# 1-TX510_KIT.net
KiCad netlist of a schematic drawn in Altium Designer
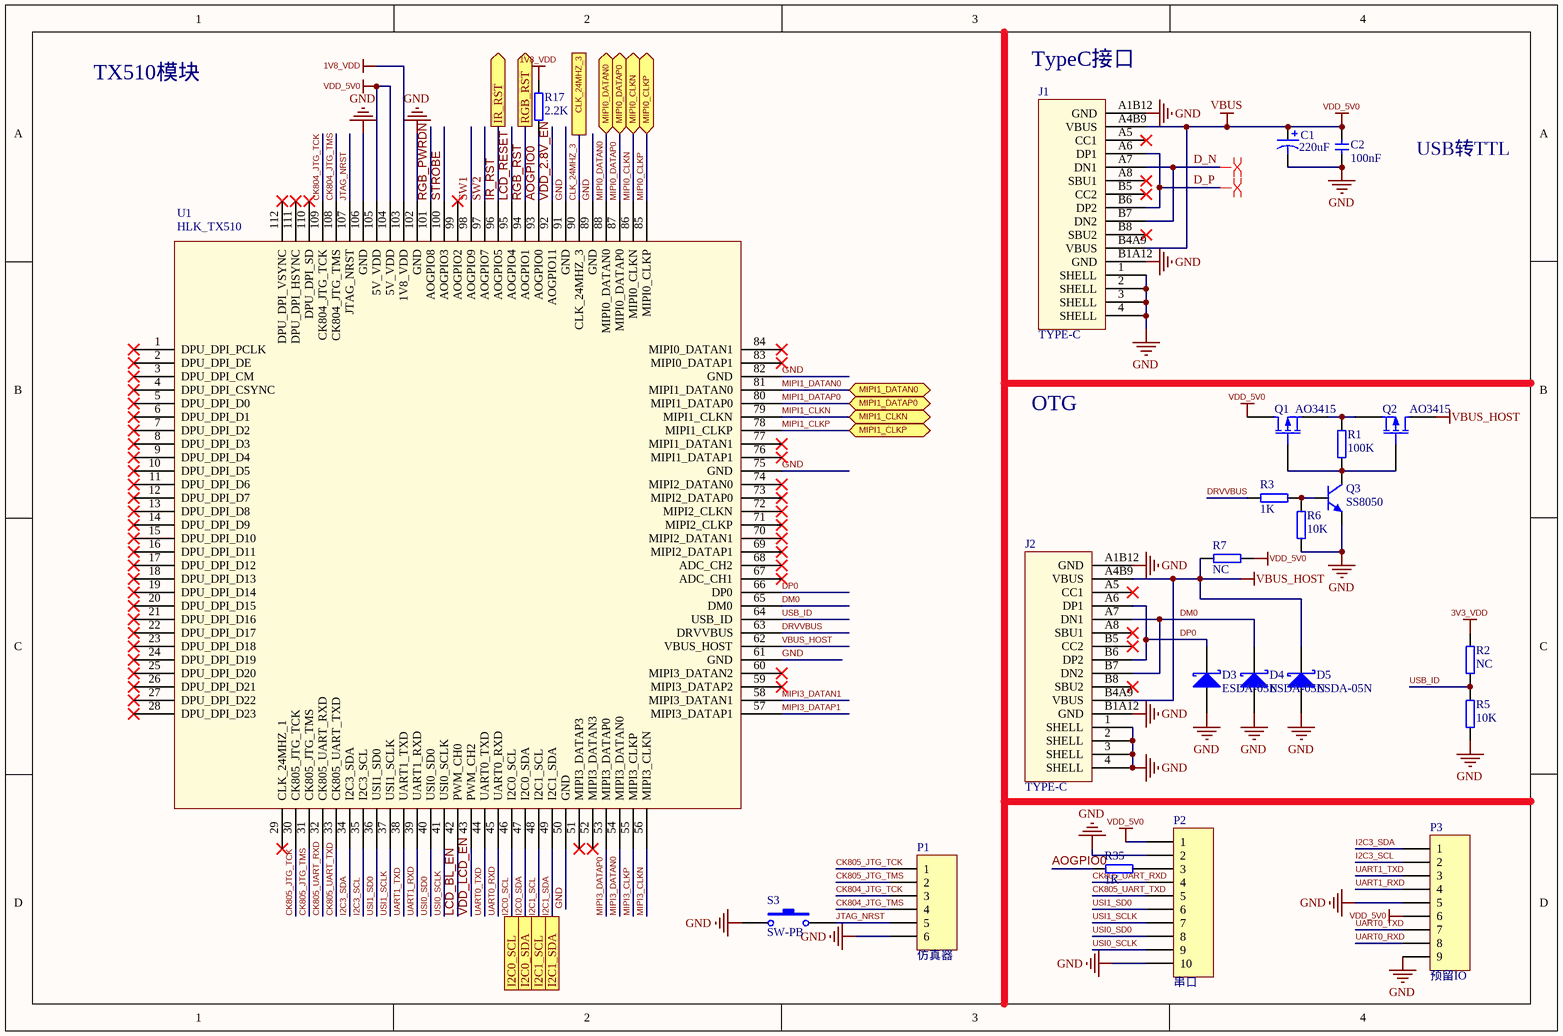
[diagram p0: 1-TX510_KIT.SchDoc]

(export (version "E")
  (design (tool "Eeschema 10.0.6"))
  (components
    (comp (ref "C1")
      (value "220uF")
      (footprint "SMD,6.3x7.7mm")
      (description "Polarized Capacitor (Radial)")
      (fields (field (name "Comment") "Cap Pol1") (field (name "PUBLISHER") "Altium Limited"))
      (libsource (lib "Miscellaneous Devices") (part "Cap Pol1"))
    )
    (comp (ref "C2")
      (value "100nF")
      (footprint "C0402")
      (description "C?")
      (libsource (lib "HNCY_SCH_Lib") (part "CAP1"))
    )
    (comp (ref "D3")
      (value "ESDA-05N")
      (footprint "R0402")
      (description "Silicon AF Schottky Diode for High-Speed Switching")
      (fields (field (name "PUBLISHER") "Altium Limited"))
      (libsource (lib "Miscellaneous Devices") (part "Diode BAS70"))
    )
    (comp (ref "D4")
      (value "ESDA-05N")
      (footprint "R0402")
      (description "Silicon AF Schottky Diode for High-Speed Switching")
      (fields (field (name "PUBLISHER") "Altium Limited"))
      (libsource (lib "Miscellaneous Devices") (part "Diode BAS70"))
    )
    (comp (ref "D5")
      (value "ESDA-05N")
      (footprint "R0402")
      (description "Silicon AF Schottky Diode for High-Speed Switching")
      (fields (field (name "PUBLISHER") "Altium Limited"))
      (libsource (lib "Miscellaneous Devices") (part "Diode BAS70"))
    )
    (comp (ref "J1") (value "TYPE-C") (footprint "TYPE-C16PIN") (libsource (lib "*") (part "TYPE-C16PIN")))
    (comp (ref "J2") (value "TYPE-C") (footprint "TYPE-C16PIN") (libsource (lib "*") (part "TYPE-C16PIN")))
    (comp (ref "P1")
      (value "仿真器")
      (footprint "HDR1X6")
      (description "Header, 6-Pin")
      (fields (field (name "PUBLISHER") "Altium Limited"))
      (libsource (lib "Miscellaneous Connectors") (part "Header 6"))
    )
    (comp (ref "P2")
      (value "串口")
      (footprint "HDR1X10")
      (description "Header, 10-Pin")
      (fields (field (name "PUBLISHER") "Altium Limited"))
      (libsource (lib "Miscellaneous Connectors") (part "Header 10"))
    )
    (comp (ref "P3")
      (value "预留IO")
      (footprint "HDR1X9")
      (description "Header, 9-Pin")
      (fields (field (name "PUBLISHER") "Altium Limited"))
      (libsource (lib "Miscellaneous Connectors") (part "Header 9"))
    )
    (comp (ref "Q1") (value "AO3415") (footprint "SOT-23") (libsource (lib "*") (part "AO3415")))
    (comp (ref "Q2") (value "AO3415") (footprint "SOT-23") (libsource (lib "*") (part "AO3415")))
    (comp (ref "Q3")
      (value "SS8050")
      (footprint "SOT23-BEC")
      (description "贴片三极管")
      (libsource (lib "HNCY_SCH_Lib") (part "NPN"))
    )
    (comp (ref "R1")
      (value "100K")
      (footprint "R0402")
      (description "R?")
      (libsource (lib "HNCY_SCH_Lib") (part "RES1"))
    )
    (comp (ref "R2")
      (value "NC")
      (footprint "R0402")
      (description "R?")
      (libsource (lib "HNCY_SCH_Lib") (part "RES1"))
    )
    (comp (ref "R3")
      (value "1K")
      (footprint "R0402")
      (description "R?")
      (libsource (lib "HNCY_SCH_Lib") (part "RES1"))
    )
    (comp (ref "R5")
      (value "10K")
      (footprint "R0402")
      (description "R?")
      (libsource (lib "HNCY_SCH_Lib") (part "RES1"))
    )
    (comp (ref "R6")
      (value "10K")
      (footprint "R0402")
      (description "R?")
      (libsource (lib "HNCY_SCH_Lib") (part "RES1"))
    )
    (comp (ref "R7")
      (value "NC")
      (footprint "RES_0603")
      (description "R?")
      (libsource (lib "HNCY_SCH_Lib") (part "RES1"))
    )
    (comp (ref "R17")
      (value "2.2K")
      (footprint "R0402")
      (description "R?")
      (libsource (lib "HNCY_SCH_Lib") (part "RES1"))
    )
    (comp (ref "R35")
      (value "1K")
      (footprint "R0402")
      (description "R?")
      (libsource (lib "HNCY_SCH_Lib") (part "RES1"))
    )
    (comp (ref "S3")
      (value "SW-PB")
      (footprint "轻触开关4.5x4.5")
      (description "Switch")
      (fields (field (name "PUBLISHER") "Altium Limited"))
      (libsource (lib "Miscellaneous Devices") (part "SW-PB"))
    )
    (comp (ref "U1")
      (value "HLK_TX510")
      (footprint "HLK_TX510 _KIT")
      (libsource (lib "MY SCHLIB") (part "HLK_TX510"))
    )
  )
  (nets
    (net (code "1") (name "/AOGPIO0") (class "Default")
      (node (ref "R17") (pin "1") (pinfunction "1_1") (pintype "passive"))
      (node (ref "R35") (pin "2") (pinfunction "2_2") (pintype "passive"))
      (node (ref "U1") (pin "93") (pinfunction "AOGPIO0_93") (pintype "passive"))
    )
    (net (code "2") (name "/CK804_JTG_TCK") (class "Default")
      (node (ref "P1") (pin "3") (pinfunction "3_3") (pintype "passive"))
      (node (ref "U1") (pin "109") (pinfunction "CK804_JTG_TCK_109") (pintype "passive"))
    )
    (net (code "3") (name "/CK804_JTG_TMS") (class "Default")
      (node (ref "P1") (pin "4") (pinfunction "4_4") (pintype "passive"))
      (node (ref "U1") (pin "108") (pinfunction "CK804_JTG_TMS_108") (pintype "passive"))
    )
    (net (code "4") (name "/CK805_JTG_TCK") (class "Default")
      (node (ref "P1") (pin "1") (pinfunction "1_1") (pintype "passive"))
      (node (ref "U1") (pin "30") (pinfunction "CK805_JTG_TCK_30") (pintype "passive"))
    )
    (net (code "5") (name "/CK805_JTG_TMS") (class "Default")
      (node (ref "P1") (pin "2") (pinfunction "2_2") (pintype "passive"))
      (node (ref "U1") (pin "31") (pinfunction "CK805_JTG_TMS_31") (pintype "passive"))
    )
    (net (code "6") (name "/CK805_UART_RXD") (class "Default")
      (node (ref "P2") (pin "4") (pinfunction "4_4") (pintype "passive"))
      (node (ref "U1") (pin "32") (pinfunction "CK805_UART_RXD_32") (pintype "passive"))
    )
    (net (code "7") (name "/CK805_UART_TXD") (class "Default")
      (node (ref "P2") (pin "5") (pinfunction "5_5") (pintype "passive"))
      (node (ref "U1") (pin "33") (pinfunction "CK805_UART_TXD_33") (pintype "passive"))
    )
    (net (code "8") (name "/CLK_24MHZ_3") (class "Default")
      (node (ref "U1") (pin "90") (pinfunction "CLK_24MHZ_3_90") (pintype "passive"))
    )
    (net (code "9") (name "/DM0") (class "Default")
      (node (ref "D4") (pin "2") (pinfunction "K_2") (pintype "passive"))
      (node (ref "J2") (pin "A7") (pinfunction "DN1_A7") (pintype "passive"))
      (node (ref "J2") (pin "B7") (pinfunction "DN2_B7") (pintype "passive"))
      (node (ref "U1") (pin "65") (pinfunction "DM0_65") (pintype "passive"))
    )
    (net (code "10") (name "/DP0") (class "Default")
      (node (ref "D3") (pin "2") (pinfunction "K_2") (pintype "passive"))
      (node (ref "J2") (pin "A6") (pinfunction "DP1_A6") (pintype "passive"))
      (node (ref "J2") (pin "B6") (pinfunction "DP2_B6") (pintype "passive"))
      (node (ref "U1") (pin "66") (pinfunction "DP0_66") (pintype "passive"))
    )
    (net (code "11") (name "/DRVVBUS") (class "Default")
      (node (ref "R3") (pin "2") (pinfunction "2_2") (pintype "passive"))
      (node (ref "U1") (pin "63") (pinfunction "DRVVBUS_63") (pintype "passive"))
    )
    (net (code "12") (name "/D_N") (class "Default")
      (node (ref "J1") (pin "A7") (pinfunction "DN1_A7") (pintype "passive"))
      (node (ref "J1") (pin "B7") (pinfunction "DN2_B7") (pintype "passive"))
    )
    (net (code "13") (name "/D_P") (class "Default")
      (node (ref "J1") (pin "A6") (pinfunction "DP1_A6") (pintype "passive"))
      (node (ref "J1") (pin "B6") (pinfunction "DP2_B6") (pintype "passive"))
    )
    (net (code "14") (name "/I2C0_SCL") (class "Default")
      (node (ref "U1") (pin "46") (pinfunction "I2C0_SCL_46") (pintype "passive"))
    )
    (net (code "15") (name "/I2C0_SDA") (class "Default")
      (node (ref "U1") (pin "47") (pinfunction "I2C0_SDA_47") (pintype "passive"))
    )
    (net (code "16") (name "/I2C1_SCL") (class "Default")
      (node (ref "U1") (pin "48") (pinfunction "I2C1_SCL_48") (pintype "passive"))
    )
    (net (code "17") (name "/I2C1_SDA") (class "Default")
      (node (ref "U1") (pin "49") (pinfunction "I2C1_SDA_49") (pintype "passive"))
    )
    (net (code "18") (name "/I2C3_SCL") (class "Default")
      (node (ref "P3") (pin "2") (pinfunction "2_2") (pintype "passive"))
      (node (ref "U1") (pin "35") (pinfunction "I2C3_SCL_35") (pintype "passive"))
    )
    (net (code "19") (name "/I2C3_SDA") (class "Default")
      (node (ref "P3") (pin "1") (pinfunction "1_1") (pintype "passive"))
      (node (ref "U1") (pin "34") (pinfunction "I2C3_SDA_34") (pintype "passive"))
    )
    (net (code "20") (name "/IR_RST") (class "Default")
      (node (ref "U1") (pin "96") (pinfunction "AOGPIO5_96") (pintype "passive"))
    )
    (net (code "21") (name "/JTAG_NRST") (class "Default")
      (node (ref "P1") (pin "5") (pinfunction "5_5") (pintype "passive"))
      (node (ref "S3") (pin "2") (pinfunction "2_2") (pintype "passive"))
      (node (ref "U1") (pin "107") (pinfunction "JTAG_NRST_107") (pintype "passive"))
    )
    (net (code "22") (name "/LCD_BL_EN") (class "Default")
      (node (ref "U1") (pin "42") (pinfunction "PWM_CH0_42") (pintype "passive"))
    )
    (net (code "23") (name "/LCD_RESET") (class "Default")
      (node (ref "U1") (pin "95") (pinfunction "AOGPIO4_95") (pintype "passive"))
    )
    (net (code "24") (name "/MIPI0_CLKN") (class "Default")
      (node (ref "U1") (pin "86") (pinfunction "MIPI0_CLKN_86") (pintype "passive"))
    )
    (net (code "25") (name "/MIPI0_CLKP") (class "Default")
      (node (ref "U1") (pin "85") (pinfunction "MIPI0_CLKP_85") (pintype "passive"))
    )
    (net (code "26") (name "/MIPI0_DATAN0") (class "Default")
      (node (ref "U1") (pin "88") (pinfunction "MIPI0_DATAN0_88") (pintype "passive"))
    )
    (net (code "27") (name "/MIPI0_DATAP0") (class "Default")
      (node (ref "U1") (pin "87") (pinfunction "MIPI0_DATAP0_87") (pintype "passive"))
    )
    (net (code "28") (name "/MIPI1_CLKN") (class "Default")
      (node (ref "U1") (pin "79") (pinfunction "MIPI1_CLKN_79") (pintype "passive"))
    )
    (net (code "29") (name "/MIPI1_CLKP") (class "Default")
      (node (ref "U1") (pin "78") (pinfunction "MIPI1_CLKP_78") (pintype "passive"))
    )
    (net (code "30") (name "/MIPI1_DATAN0") (class "Default")
      (node (ref "U1") (pin "81") (pinfunction "MIPI1_DATAN0_81") (pintype "passive"))
    )
    (net (code "31") (name "/MIPI1_DATAP0") (class "Default")
      (node (ref "U1") (pin "80") (pinfunction "MIPI1_DATAP0_80") (pintype "passive"))
    )
    (net (code "32") (name "/MIPI3_CLKN") (class "Default")
      (node (ref "U1") (pin "56") (pinfunction "MIPI3_CLKN_56") (pintype "passive"))
    )
    (net (code "33") (name "/MIPI3_CLKP") (class "Default")
      (node (ref "U1") (pin "55") (pinfunction "MIPI3_CLKP_55") (pintype "passive"))
    )
    (net (code "34") (name "/MIPI3_DATAN0") (class "Default")
      (node (ref "U1") (pin "54") (pinfunction "MIPI3_DATAN0_54") (pintype "passive"))
    )
    (net (code "35") (name "/MIPI3_DATAN1") (class "Default")
      (node (ref "U1") (pin "58") (pinfunction "MIPI3_DATAN1_58") (pintype "passive"))
    )
    (net (code "36") (name "/MIPI3_DATAP0") (class "Default")
      (node (ref "U1") (pin "53") (pinfunction "MIPI3_DATAP0_53") (pintype "passive"))
    )
    (net (code "37") (name "/MIPI3_DATAP1") (class "Default")
      (node (ref "U1") (pin "57") (pinfunction "MIPI3_DATAP1_57") (pintype "passive"))
    )
    (net (code "38") (name "/RGB_PWRDN") (class "Default")
      (node (ref "U1") (pin "101") (pinfunction "AOGPIO8_101") (pintype "passive"))
    )
    (net (code "39") (name "/RGB_RST") (class "Default")
      (node (ref "U1") (pin "94") (pinfunction "AOGPIO1_94") (pintype "passive"))
    )
    (net (code "40") (name "/STROBE") (class "Default")
      (node (ref "U1") (pin "100") (pinfunction "AOGPIO3_100") (pintype "passive"))
    )
    (net (code "41") (name "/SW1") (class "Default")
      (node (ref "U1") (pin "98") (pinfunction "AOGPIO9_98") (pintype "passive"))
    )
    (net (code "42") (name "/SW2") (class "Default")
      (node (ref "U1") (pin "97") (pinfunction "AOGPIO7_97") (pintype "passive"))
    )
    (net (code "43") (name "/UART0_RXD") (class "Default")
      (node (ref "P3") (pin "8") (pinfunction "8_8") (pintype "passive"))
      (node (ref "U1") (pin "45") (pinfunction "UART0_RXD_45") (pintype "passive"))
    )
    (net (code "44") (name "/UART0_TXD") (class "Default")
      (node (ref "P3") (pin "7") (pinfunction "7_7") (pintype "passive"))
      (node (ref "U1") (pin "44") (pinfunction "UART0_TXD_44") (pintype "passive"))
    )
    (net (code "45") (name "/UART1_RXD") (class "Default")
      (node (ref "P3") (pin "4") (pinfunction "4_4") (pintype "passive"))
      (node (ref "U1") (pin "39") (pinfunction "UART1_RXD_39") (pintype "passive"))
    )
    (net (code "46") (name "/UART1_TXD") (class "Default")
      (node (ref "P3") (pin "3") (pinfunction "3_3") (pintype "passive"))
      (node (ref "U1") (pin "38") (pinfunction "UART1_TXD_38") (pintype "passive"))
    )
    (net (code "47") (name "/USB_ID") (class "Default")
      (node (ref "R2") (pin "1") (pinfunction "1_1") (pintype "passive"))
      (node (ref "R5") (pin "2") (pinfunction "2_2") (pintype "passive"))
      (node (ref "U1") (pin "64") (pinfunction "USB_ID_64") (pintype "passive"))
    )
    (net (code "48") (name "/USI0_SCLK") (class "Default")
      (node (ref "P2") (pin "9") (pinfunction "9_9") (pintype "passive"))
      (node (ref "U1") (pin "41") (pinfunction "USI0_SCLK_41") (pintype "passive"))
    )
    (net (code "49") (name "/USI0_SD0") (class "Default")
      (node (ref "P2") (pin "8") (pinfunction "8_8") (pintype "passive"))
      (node (ref "U1") (pin "40") (pinfunction "USI0_SD0_40") (pintype "passive"))
    )
    (net (code "50") (name "/USI1_SCLK") (class "Default")
      (node (ref "P2") (pin "7") (pinfunction "7_7") (pintype "passive"))
      (node (ref "U1") (pin "37") (pinfunction "USI1_SCLK_37") (pintype "passive"))
    )
    (net (code "51") (name "/USI1_SD0") (class "Default")
      (node (ref "P2") (pin "6") (pinfunction "6_6") (pintype "passive"))
      (node (ref "U1") (pin "36") (pinfunction "USI1_SD0_36") (pintype "passive"))
    )
    (net (code "52") (name "/VDD_2.8V_EN") (class "Default")
      (node (ref "U1") (pin "92") (pinfunction "AOGPIO11_92") (pintype "passive"))
    )
    (net (code "53") (name "/VDD_LCD_EN") (class "Default")
      (node (ref "U1") (pin "43") (pinfunction "PWM_CH2_43") (pintype "passive"))
    )
    (net (code "54") (name "1V8_VDD") (class "Default")
      (node (ref "R17") (pin "2") (pinfunction "2_2") (pintype "passive"))
      (node (ref "U1") (pin "103") (pinfunction "1V8_VDD_103") (pintype "passive"))
    )
    (net (code "55") (name "3V3_VDD") (class "Default")
      (node (ref "R2") (pin "2") (pinfunction "2_2") (pintype "passive"))
    )
    (net (code "56") (name "GND") (class "Default")
      (node (ref "C1") (pin "2") (pinfunction "2_2") (pintype "passive"))
      (node (ref "C2") (pin "1") (pintype "passive"))
      (node (ref "D3") (pin "1") (pinfunction "A_1") (pintype "passive"))
      (node (ref "D4") (pin "1") (pinfunction "A_1") (pintype "passive"))
      (node (ref "D5") (pin "1") (pinfunction "A_1") (pintype "passive"))
      (node (ref "J1") (pin "1") (pinfunction "SHELL_1") (pintype "passive"))
      (node (ref "J1") (pin "2") (pinfunction "SHELL_2") (pintype "passive"))
      (node (ref "J1") (pin "3") (pinfunction "SHELL_3") (pintype "passive"))
      (node (ref "J1") (pin "4") (pinfunction "SHELL_4") (pintype "passive"))
      (node (ref "J1") (pin "A1B12") (pinfunction "GND_A1B12") (pintype "passive"))
      (node (ref "J1") (pin "B1A12") (pinfunction "GND_B1A12") (pintype "passive"))
      (node (ref "J2") (pin "1") (pinfunction "SHELL_1") (pintype "passive"))
      (node (ref "J2") (pin "2") (pinfunction "SHELL_2") (pintype "passive"))
      (node (ref "J2") (pin "3") (pinfunction "SHELL_3") (pintype "passive"))
      (node (ref "J2") (pin "4") (pinfunction "SHELL_4") (pintype "passive"))
      (node (ref "J2") (pin "A1B12") (pinfunction "GND_A1B12") (pintype "passive"))
      (node (ref "J2") (pin "B1A12") (pinfunction "GND_B1A12") (pintype "passive"))
      (node (ref "P1") (pin "6") (pinfunction "6_6") (pintype "passive"))
      (node (ref "P2") (pin "10") (pinfunction "10_10") (pintype "passive"))
      (node (ref "P2") (pin "2") (pinfunction "2_2") (pintype "passive"))
      (node (ref "P3") (pin "5") (pinfunction "5_5") (pintype "passive"))
      (node (ref "P3") (pin "9") (pinfunction "9_9") (pintype "passive"))
      (node (ref "Q3") (pin "E") (pinfunction "E_E") (pintype "passive"))
      (node (ref "R5") (pin "1") (pinfunction "1_1") (pintype "passive"))
      (node (ref "R6") (pin "1") (pinfunction "1_1") (pintype "passive"))
      (node (ref "S3") (pin "1") (pinfunction "1_1") (pintype "passive"))
      (node (ref "U1") (pin "102") (pinfunction "GND_102") (pintype "passive"))
      (node (ref "U1") (pin "106") (pinfunction "GND_106") (pintype "passive"))
      (node (ref "U1") (pin "50") (pinfunction "GND_50") (pintype "passive"))
      (node (ref "U1") (pin "61") (pinfunction "GND_61") (pintype "passive"))
      (node (ref "U1") (pin "75") (pinfunction "GND_75") (pintype "passive"))
      (node (ref "U1") (pin "82") (pinfunction "GND_82") (pintype "passive"))
      (node (ref "U1") (pin "89") (pinfunction "GND_89") (pintype "passive"))
      (node (ref "U1") (pin "91") (pinfunction "GND_91") (pintype "passive"))
    )
    (net (code "57") (name "Net-(P2-Pad3)") (class "Default")
      (node (ref "P2") (pin "3") (pinfunction "3_3") (pintype "passive"))
      (node (ref "R35") (pin "1") (pinfunction "1_1") (pintype "passive"))
    )
    (net (code "58") (name "Net-(Q1-G)") (class "Default")
      (node (ref "Q1") (pin "1") (pinfunction "G_1") (pintype "passive"))
      (node (ref "Q2") (pin "1") (pinfunction "G_1") (pintype "passive"))
      (node (ref "Q3") (pin "C") (pinfunction "C_C") (pintype "passive"))
      (node (ref "R1") (pin "1") (pinfunction "1_1") (pintype "passive"))
    )
    (net (code "59") (name "Net-(Q1-S)") (class "Default")
      (node (ref "Q1") (pin "2") (pinfunction "S_2") (pintype "passive"))
      (node (ref "Q2") (pin "2") (pinfunction "S_2") (pintype "passive"))
      (node (ref "R1") (pin "2") (pinfunction "2_2") (pintype "passive"))
    )
    (net (code "60") (name "Net-(Q3-PadB)") (class "Default")
      (node (ref "Q3") (pin "B") (pinfunction "B_B") (pintype "passive"))
      (node (ref "R3") (pin "1") (pinfunction "1_1") (pintype "passive"))
      (node (ref "R6") (pin "2") (pinfunction "2_2") (pintype "passive"))
    )
    (net (code "61") (name "VBUS") (class "Default")
      (node (ref "C1") (pin "1") (pinfunction "1_1") (pintype "passive"))
      (node (ref "C2") (pin "2") (pintype "passive"))
      (node (ref "J1") (pin "A4B9") (pinfunction "VBUS_A4B9") (pintype "passive"))
      (node (ref "J1") (pin "B4A9") (pinfunction "VBUS_B4A9") (pintype "passive"))
      (node (ref "P2") (pin "1") (pinfunction "1_1") (pintype "passive"))
      (node (ref "P3") (pin "6") (pinfunction "6_6") (pintype "passive"))
      (node (ref "Q1") (pin "3") (pinfunction "D_3") (pintype "passive"))
      (node (ref "R7") (pin "1") (pinfunction "1_1") (pintype "passive"))
      (node (ref "U1") (pin "104") (pinfunction "5V_VDD_104") (pintype "passive"))
      (node (ref "U1") (pin "105") (pinfunction "5V_VDD_105") (pintype "passive"))
    )
    (net (code "62") (name "VBUS_HOST") (class "Default")
      (node (ref "D5") (pin "2") (pinfunction "K_2") (pintype "passive"))
      (node (ref "J2") (pin "A4B9") (pinfunction "VBUS_A4B9") (pintype "passive"))
      (node (ref "J2") (pin "B4A9") (pinfunction "VBUS_B4A9") (pintype "passive"))
      (node (ref "Q2") (pin "3") (pinfunction "D_3") (pintype "passive"))
      (node (ref "R7") (pin "2") (pinfunction "2_2") (pintype "passive"))
      (node (ref "U1") (pin "62") (pinfunction "VBUS_HOST_62") (pintype "passive"))
    )
    (net (code "63") (name "unconnected-(J1-CC1-PadA5)") (class "Default")
      (node (ref "J1") (pin "A5") (pinfunction "CC1_A5") (pintype "passive+no_connect"))
    )
    (net (code "64") (name "unconnected-(J1-CC2-PadB5)") (class "Default")
      (node (ref "J1") (pin "B5") (pinfunction "CC2_B5") (pintype "passive+no_connect"))
    )
    (net (code "65") (name "unconnected-(J1-SBU1-PadA8)") (class "Default")
      (node (ref "J1") (pin "A8") (pinfunction "SBU1_A8") (pintype "passive+no_connect"))
    )
    (net (code "66") (name "unconnected-(J1-SBU2-PadB8)") (class "Default")
      (node (ref "J1") (pin "B8") (pinfunction "SBU2_B8") (pintype "passive+no_connect"))
    )
    (net (code "67") (name "unconnected-(J2-CC1-PadA5)") (class "Default")
      (node (ref "J2") (pin "A5") (pinfunction "CC1_A5") (pintype "passive+no_connect"))
    )
    (net (code "68") (name "unconnected-(J2-CC2-PadB5)") (class "Default")
      (node (ref "J2") (pin "B5") (pinfunction "CC2_B5") (pintype "passive+no_connect"))
    )
    (net (code "69") (name "unconnected-(J2-SBU1-PadA8)") (class "Default")
      (node (ref "J2") (pin "A8") (pinfunction "SBU1_A8") (pintype "passive+no_connect"))
    )
    (net (code "70") (name "unconnected-(J2-SBU2-PadB8)") (class "Default")
      (node (ref "J2") (pin "B8") (pinfunction "SBU2_B8") (pintype "passive+no_connect"))
    )
    (net (code "71") (name "unconnected-(U1-ADC_CH1-Pad67)") (class "Default")
      (node (ref "U1") (pin "67") (pinfunction "ADC_CH1_67") (pintype "passive+no_connect"))
    )
    (net (code "72") (name "unconnected-(U1-ADC_CH2-Pad68)") (class "Default")
      (node (ref "U1") (pin "68") (pinfunction "ADC_CH2_68") (pintype "passive+no_connect"))
    )
    (net (code "73") (name "unconnected-(U1-AOGPIO2-Pad99)") (class "Default")
      (node (ref "U1") (pin "99") (pinfunction "AOGPIO2_99") (pintype "passive+no_connect"))
    )
    (net (code "74") (name "unconnected-(U1-CLK_24MHZ_1-Pad29)") (class "Default")
      (node (ref "U1") (pin "29") (pinfunction "CLK_24MHZ_1_29") (pintype "passive+no_connect"))
    )
    (net (code "75") (name "unconnected-(U1-DPU_DPI_CM-Pad3)") (class "Default")
      (node (ref "U1") (pin "3") (pinfunction "DPU_DPI_CM_3") (pintype "passive+no_connect"))
    )
    (net (code "76") (name "unconnected-(U1-DPU_DPI_CSYNC-Pad4)") (class "Default")
      (node (ref "U1") (pin "4") (pinfunction "DPU_DPI_CSYNC_4") (pintype "passive+no_connect"))
    )
    (net (code "77") (name "unconnected-(U1-DPU_DPI_D0-Pad5)") (class "Default")
      (node (ref "U1") (pin "5") (pinfunction "DPU_DPI_D0_5") (pintype "passive+no_connect"))
    )
    (net (code "78") (name "unconnected-(U1-DPU_DPI_D1-Pad6)") (class "Default")
      (node (ref "U1") (pin "6") (pinfunction "DPU_DPI_D1_6") (pintype "passive+no_connect"))
    )
    (net (code "79") (name "unconnected-(U1-DPU_DPI_D2-Pad7)") (class "Default")
      (node (ref "U1") (pin "7") (pinfunction "DPU_DPI_D2_7") (pintype "passive+no_connect"))
    )
    (net (code "80") (name "unconnected-(U1-DPU_DPI_D3-Pad8)") (class "Default")
      (node (ref "U1") (pin "8") (pinfunction "DPU_DPI_D3_8") (pintype "passive+no_connect"))
    )
    (net (code "81") (name "unconnected-(U1-DPU_DPI_D4-Pad9)") (class "Default")
      (node (ref "U1") (pin "9") (pinfunction "DPU_DPI_D4_9") (pintype "passive+no_connect"))
    )
    (net (code "82") (name "unconnected-(U1-DPU_DPI_D5-Pad10)") (class "Default")
      (node (ref "U1") (pin "10") (pinfunction "DPU_DPI_D5_10") (pintype "passive+no_connect"))
    )
    (net (code "83") (name "unconnected-(U1-DPU_DPI_D6-Pad11)") (class "Default")
      (node (ref "U1") (pin "11") (pinfunction "DPU_DPI_D6_11") (pintype "passive+no_connect"))
    )
    (net (code "84") (name "unconnected-(U1-DPU_DPI_D7-Pad12)") (class "Default")
      (node (ref "U1") (pin "12") (pinfunction "DPU_DPI_D7_12") (pintype "passive+no_connect"))
    )
    (net (code "85") (name "unconnected-(U1-DPU_DPI_D8-Pad13)") (class "Default")
      (node (ref "U1") (pin "13") (pinfunction "DPU_DPI_D8_13") (pintype "passive+no_connect"))
    )
    (net (code "86") (name "unconnected-(U1-DPU_DPI_D9-Pad14)") (class "Default")
      (node (ref "U1") (pin "14") (pinfunction "DPU_DPI_D9_14") (pintype "passive+no_connect"))
    )
    (net (code "87") (name "unconnected-(U1-DPU_DPI_D10-Pad15)") (class "Default")
      (node (ref "U1") (pin "15") (pinfunction "DPU_DPI_D10_15") (pintype "passive+no_connect"))
    )
    (net (code "88") (name "unconnected-(U1-DPU_DPI_D11-Pad16)") (class "Default")
      (node (ref "U1") (pin "16") (pinfunction "DPU_DPI_D11_16") (pintype "passive+no_connect"))
    )
    (net (code "89") (name "unconnected-(U1-DPU_DPI_D12-Pad17)") (class "Default")
      (node (ref "U1") (pin "17") (pinfunction "DPU_DPI_D12_17") (pintype "passive+no_connect"))
    )
    (net (code "90") (name "unconnected-(U1-DPU_DPI_D13-Pad18)") (class "Default")
      (node (ref "U1") (pin "18") (pinfunction "DPU_DPI_D13_18") (pintype "passive+no_connect"))
    )
    (net (code "91") (name "unconnected-(U1-DPU_DPI_D14-Pad19)") (class "Default")
      (node (ref "U1") (pin "19") (pinfunction "DPU_DPI_D14_19") (pintype "passive+no_connect"))
    )
    (net (code "92") (name "unconnected-(U1-DPU_DPI_D15-Pad20)") (class "Default")
      (node (ref "U1") (pin "20") (pinfunction "DPU_DPI_D15_20") (pintype "passive+no_connect"))
    )
    (net (code "93") (name "unconnected-(U1-DPU_DPI_D16-Pad21)") (class "Default")
      (node (ref "U1") (pin "21") (pinfunction "DPU_DPI_D16_21") (pintype "passive+no_connect"))
    )
    (net (code "94") (name "unconnected-(U1-DPU_DPI_D17-Pad22)") (class "Default")
      (node (ref "U1") (pin "22") (pinfunction "DPU_DPI_D17_22") (pintype "passive+no_connect"))
    )
    (net (code "95") (name "unconnected-(U1-DPU_DPI_D18-Pad23)") (class "Default")
      (node (ref "U1") (pin "23") (pinfunction "DPU_DPI_D18_23") (pintype "passive+no_connect"))
    )
    (net (code "96") (name "unconnected-(U1-DPU_DPI_D19-Pad24)") (class "Default")
      (node (ref "U1") (pin "24") (pinfunction "DPU_DPI_D19_24") (pintype "passive+no_connect"))
    )
    (net (code "97") (name "unconnected-(U1-DPU_DPI_D20-Pad25)") (class "Default")
      (node (ref "U1") (pin "25") (pinfunction "DPU_DPI_D20_25") (pintype "passive+no_connect"))
    )
    (net (code "98") (name "unconnected-(U1-DPU_DPI_D21-Pad26)") (class "Default")
      (node (ref "U1") (pin "26") (pinfunction "DPU_DPI_D21_26") (pintype "passive+no_connect"))
    )
    (net (code "99") (name "unconnected-(U1-DPU_DPI_D22-Pad27)") (class "Default")
      (node (ref "U1") (pin "27") (pinfunction "DPU_DPI_D22_27") (pintype "passive+no_connect"))
    )
    (net (code "100") (name "unconnected-(U1-DPU_DPI_D23-Pad28)") (class "Default")
      (node (ref "U1") (pin "28") (pinfunction "DPU_DPI_D23_28") (pintype "passive+no_connect"))
    )
    (net (code "101") (name "unconnected-(U1-DPU_DPI_DE-Pad2)") (class "Default")
      (node (ref "U1") (pin "2") (pinfunction "DPU_DPI_DE_2") (pintype "passive+no_connect"))
    )
    (net (code "102") (name "unconnected-(U1-DPU_DPI_HSYNC-Pad111)") (class "Default")
      (node (ref "U1") (pin "111") (pinfunction "DPU_DPI_HSYNC_111") (pintype "passive+no_connect"))
    )
    (net (code "103") (name "unconnected-(U1-DPU_DPI_PCLK-Pad1)") (class "Default")
      (node (ref "U1") (pin "1") (pinfunction "DPU_DPI_PCLK_1") (pintype "passive+no_connect"))
    )
    (net (code "104") (name "unconnected-(U1-DPU_DPI_SD-Pad110)") (class "Default")
      (node (ref "U1") (pin "110") (pinfunction "DPU_DPI_SD_110") (pintype "passive+no_connect"))
    )
    (net (code "105") (name "unconnected-(U1-DPU_DPI_VSYNC-Pad112)") (class "Default")
      (node (ref "U1") (pin "112") (pinfunction "DPU_DPI_VSYNC_112") (pintype "passive+no_connect"))
    )
    (net (code "106") (name "unconnected-(U1-MIPI0_DATAN1-Pad84)") (class "Default")
      (node (ref "U1") (pin "84") (pinfunction "MIPI0_DATAN1_84") (pintype "passive+no_connect"))
    )
    (net (code "107") (name "unconnected-(U1-MIPI0_DATAP1-Pad83)") (class "Default")
      (node (ref "U1") (pin "83") (pinfunction "MIPI0_DATAP1_83") (pintype "passive+no_connect"))
    )
    (net (code "108") (name "unconnected-(U1-MIPI1_DATAN1-Pad77)") (class "Default")
      (node (ref "U1") (pin "77") (pinfunction "MIPI1_DATAN1_77") (pintype "passive+no_connect"))
    )
    (net (code "109") (name "unconnected-(U1-MIPI1_DATAP1-Pad76)") (class "Default")
      (node (ref "U1") (pin "76") (pinfunction "MIPI1_DATAP1_76") (pintype "passive+no_connect"))
    )
    (net (code "110") (name "unconnected-(U1-MIPI2_CLKN-Pad72)") (class "Default")
      (node (ref "U1") (pin "72") (pinfunction "MIPI2_CLKN_72") (pintype "passive+no_connect"))
    )
    (net (code "111") (name "unconnected-(U1-MIPI2_CLKP-Pad71)") (class "Default")
      (node (ref "U1") (pin "71") (pinfunction "MIPI2_CLKP_71") (pintype "passive+no_connect"))
    )
    (net (code "112") (name "unconnected-(U1-MIPI2_DATAN0-Pad74)") (class "Default")
      (node (ref "U1") (pin "74") (pinfunction "MIPI2_DATAN0_74") (pintype "passive+no_connect"))
    )
    (net (code "113") (name "unconnected-(U1-MIPI2_DATAN1-Pad70)") (class "Default")
      (node (ref "U1") (pin "70") (pinfunction "MIPI2_DATAN1_70") (pintype "passive+no_connect"))
    )
    (net (code "114") (name "unconnected-(U1-MIPI2_DATAP0-Pad73)") (class "Default")
      (node (ref "U1") (pin "73") (pinfunction "MIPI2_DATAP0_73") (pintype "passive+no_connect"))
    )
    (net (code "115") (name "unconnected-(U1-MIPI2_DATAP1-Pad69)") (class "Default")
      (node (ref "U1") (pin "69") (pinfunction "MIPI2_DATAP1_69") (pintype "passive+no_connect"))
    )
    (net (code "116") (name "unconnected-(U1-MIPI3_DATAN2-Pad60)") (class "Default")
      (node (ref "U1") (pin "60") (pinfunction "MIPI3_DATAN2_60") (pintype "passive+no_connect"))
    )
    (net (code "117") (name "unconnected-(U1-MIPI3_DATAN3-Pad52)") (class "Default")
      (node (ref "U1") (pin "52") (pinfunction "MIPI3_DATAN3_52") (pintype "passive+no_connect"))
    )
    (net (code "118") (name "unconnected-(U1-MIPI3_DATAP2-Pad59)") (class "Default")
      (node (ref "U1") (pin "59") (pinfunction "MIPI3_DATAP2_59") (pintype "passive+no_connect"))
    )
    (net (code "119") (name "unconnected-(U1-MIPI3_DATAP3-Pad51)") (class "Default")
      (node (ref "U1") (pin "51") (pinfunction "MIPI3_DATAP3_51") (pintype "passive+no_connect"))
    )
  )
)
